# Stepping_Motor_DriverD.net
KiCad netlist of a schematic drawn in Altium Designer
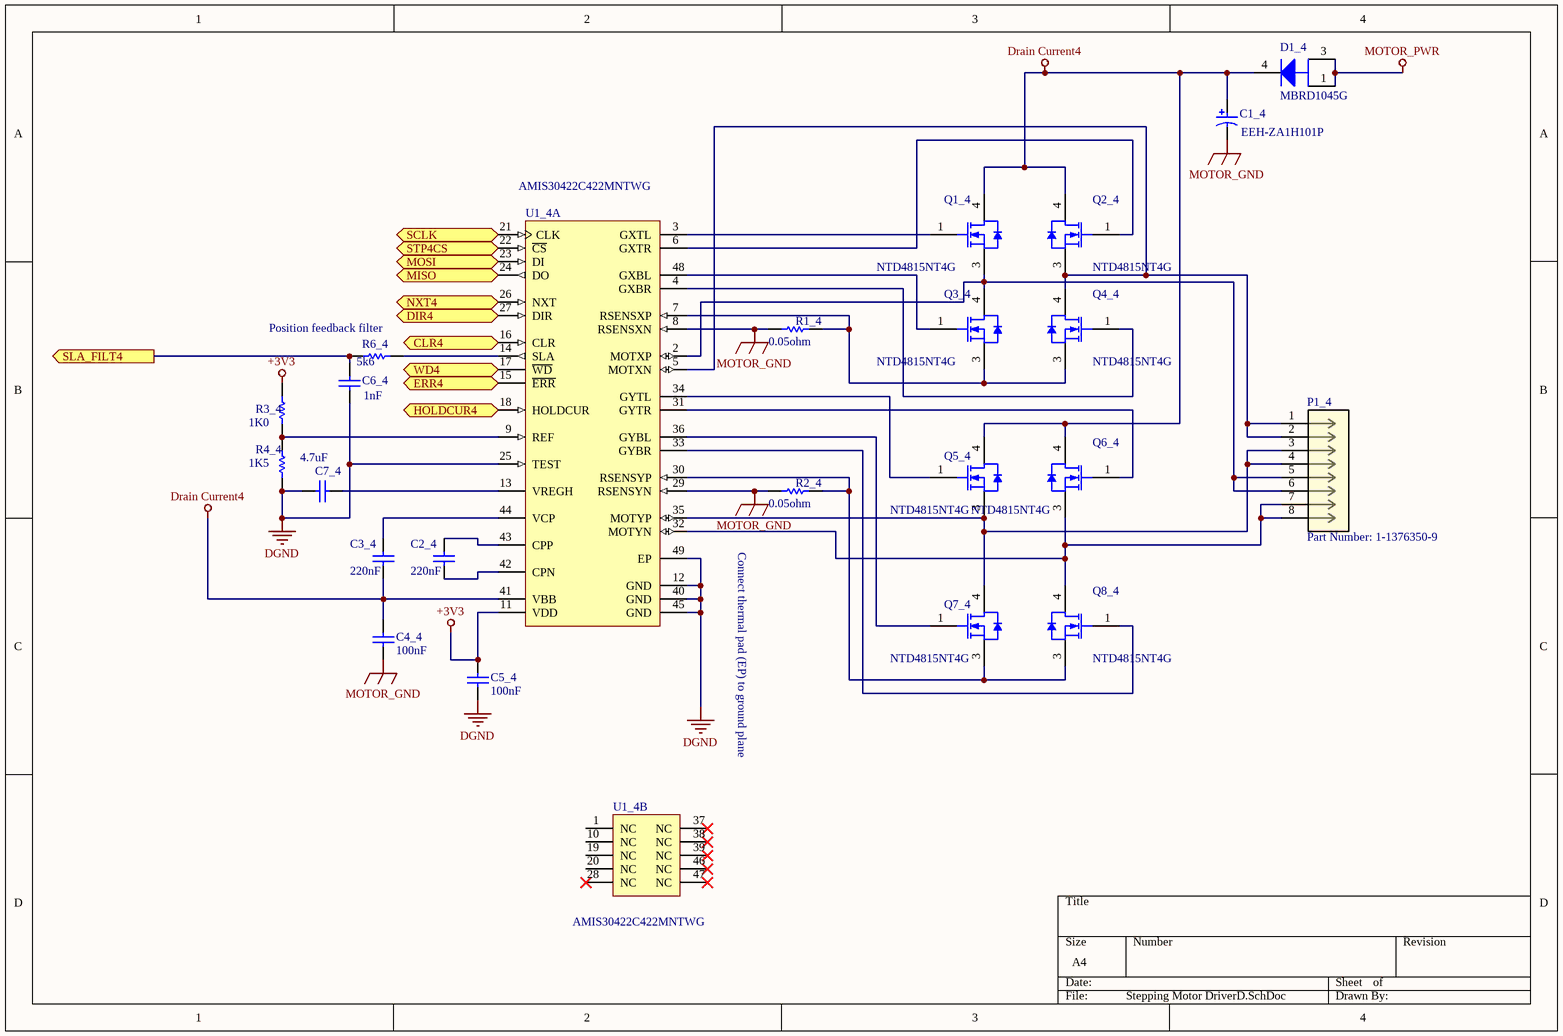
[diagram p0: Stepping Motor DriverD.SchDoc]

(export (version "E")
  (design (tool "Eeschema 10.0.6"))
  (components
    (comp (ref "C1_4")
      (value "EEH-ZA1H101P")
      (footprint "PNSC-ZA-G_L")
      (fields (field (name "TOLERANCE") "20%") (field (name "MANUFACTURER") "Panasonic"))
      (libsource (lib "Altium Content Vault") (part "CAP-P-2"))
    )
    (comp (ref "C2_4")
      (value "220nF")
      (footprint "CAPC0805(2012)75_L")
      (description "CAP 220nF 50V -20% to +80% 0805 (2012 Metric) Thickness 0.75mm SMD")
      (fields (field (name "TOLERANCE") "-20% to +80%") (field (name "Comment") "CAP 220nF 50V 0805(2012)"))
      (libsource (lib "Altium Content Vault") (part "CMP-1036-04556-1"))
    )
    (comp (ref "C3_4")
      (value "220nF")
      (footprint "CAPC0805(2012)75_L")
      (description "CAP 220nF 50V -20% to +80% 0805 (2012 Metric) Thickness 0.75mm SMD")
      (fields (field (name "TOLERANCE") "-20% to +80%") (field (name "Comment") "CAP 220nF 50V 0805(2012)"))
      (libsource (lib "Altium Content Vault") (part "CMP-1036-04556-1"))
    )
    (comp (ref "C4_4")
      (value "100nF")
      (footprint "CAPC1812(4532)110_N")
      (description "CAP 100nF 50V ±20% 1812 (4532 Metric) Thickness 1.1mm SMD")
      (fields (field (name "TOLERANCE") "Â±20%") (field (name "Comment") "CAP 100nF 50V 1812(4532)"))
      (libsource (lib "Altium Content Vault") (part "CMP-1040-01292-1"))
    )
    (comp (ref "C5_4")
      (value "100nF")
      (footprint "CAPC1812(4532)110_N")
      (description "CAP 100nF 50V ±20% 1812 (4532 Metric) Thickness 1.1mm SMD")
      (fields (field (name "TOLERANCE") "Â±20%") (field (name "Comment") "CAP 100nF 50V 1812(4532)"))
      (libsource (lib "Altium Content Vault") (part "CMP-1040-01292-1"))
    )
    (comp (ref "C6_4")
      (value "1nF")
      (footprint "CAPC1206(3216)170_N")
      (description "CAP 1nF 50V ±2% 1206 (3216 Metric) Thickness 1.7mm SMD")
      (fields (field (name "TOLERANCE") "Â±2%") (field (name "Comment") "CAP 1nF 50V 1206(3216)"))
      (libsource (lib "Altium Content Vault") (part "CMP-1037-02447-1"))
    )
    (comp (ref "C7_4")
      (value "4.7uF")
      (footprint "CAPC2220(5750)230_L")
      (description "CAP 4.7uF 50V ±10% 2220 (5750 Metric) Thickness 2.2mm SMD")
      (fields (field (name "TOLERANCE") "Â±10%") (field (name "Comment") "CAP 4.7uF 50V 2220(5750)"))
      (libsource (lib "Altium Content Vault") (part "CMP-1042-00755-1"))
    )
    (comp (ref "D1_4")
      (value "MBRD1045G")
      (footprint "ONSC-DPAK-3-369C-01_V")
      (description "SWITCHMODE(TM) Schottky Power Rectifier, 3-Pin DPAK, Pb-Free, Tube")
      (fields (field (name "MANUFACTURER") "On Semiconductor"))
      (libsource (lib "Altium Content Vault") (part "ONSC-D-A1A3K4-3_A"))
    )
    (comp (ref "P1_4")
      (value "Part Number: 1-1376350-9")
      (footprint "conn8_1-1376350-")
      (description "025 8POS CAP ASSY H TIN")
      (fields
        (field (name "MANUFACTURER_PART_NUMBER") "1-1376350-9")
        (field (name "COPYRIGHT") "Copyright (C) 2018 Accelerated Designs. All rights reserved")
      )
      (libsource (lib "2020-04-08_04-40-03") (part "1-1376350-9"))
    )
    (comp (ref "Q1_4")
      (value "NTD4815NT4G")
      (footprint "ONSC-DPAK-3-369AA-01_V")
      (description "Power MOSFET, 30 V, 35 A, Single N-Channel, 3-Pin DPAK, Pb-Free, Tape and Reel")
      (fields (field (name "MANUFACTURER") "On Semiconductor"))
      (libsource (lib "Altium Content Vault") (part "ONSC-NMOS-G1S3D4-3_B"))
    )
    (comp (ref "Q2_4")
      (value "NTD4815NT4G")
      (footprint "ONSC-DPAK-3-369AA-01_V")
      (description "Power MOSFET, 30 V, 35 A, Single N-Channel, 3-Pin DPAK, Pb-Free, Tape and Reel")
      (fields (field (name "MANUFACTURER") "On Semiconductor"))
      (libsource (lib "Altium Content Vault") (part "CMP-1058-00298-1"))
    )
    (comp (ref "Q3_4")
      (value "NTD4815NT4G")
      (footprint "ONSC-DPAK-3-369AA-01_V")
      (description "Power MOSFET, 30 V, 35 A, Single N-Channel, 3-Pin DPAK, Pb-Free, Tape and Reel")
      (fields (field (name "MANUFACTURER") "On Semiconductor"))
      (libsource (lib "Altium Content Vault") (part "ONSC-NMOS-G1S3D4-3_B"))
    )
    (comp (ref "Q4_4")
      (value "NTD4815NT4G")
      (footprint "ONSC-DPAK-3-369AA-01_V")
      (description "Power MOSFET, 30 V, 35 A, Single N-Channel, 3-Pin DPAK, Pb-Free, Tape and Reel")
      (fields (field (name "MANUFACTURER") "On Semiconductor"))
      (libsource (lib "Altium Content Vault") (part "CMP-1058-00298-1"))
    )
    (comp (ref "Q5_4")
      (value "NTD4815NT4G")
      (footprint "ONSC-DPAK-3-369AA-01_V")
      (description "Power MOSFET, 30 V, 35 A, Single N-Channel, 3-Pin DPAK, Pb-Free, Tape and Reel")
      (fields (field (name "MANUFACTURER") "On Semiconductor"))
      (libsource (lib "Altium Content Vault") (part "ONSC-NMOS-G1S3D4-3_B"))
    )
    (comp (ref "Q6_4")
      (value "NTD4815NT4G")
      (footprint "ONSC-DPAK-3-369AA-01_V")
      (description "Power MOSFET, 30 V, 35 A, Single N-Channel, 3-Pin DPAK, Pb-Free, Tape and Reel")
      (fields (field (name "MANUFACTURER") "On Semiconductor"))
      (libsource (lib "Altium Content Vault") (part "CMP-1058-00298-1"))
    )
    (comp (ref "Q7_4")
      (value "NTD4815NT4G")
      (footprint "ONSC-DPAK-3-369AA-01_V")
      (description "Power MOSFET, 30 V, 35 A, Single N-Channel, 3-Pin DPAK, Pb-Free, Tape and Reel")
      (fields (field (name "MANUFACTURER") "On Semiconductor"))
      (libsource (lib "Altium Content Vault") (part "ONSC-NMOS-G1S3D4-3_B"))
    )
    (comp (ref "Q8_4")
      (value "NTD4815NT4G")
      (footprint "ONSC-DPAK-3-369AA-01_V")
      (description "Power MOSFET, 30 V, 35 A, Single N-Channel, 3-Pin DPAK, Pb-Free, Tape and Reel")
      (fields (field (name "MANUFACTURER") "On Semiconductor"))
      (libsource (lib "Altium Content Vault") (part "CMP-1058-00298-1"))
    )
    (comp (ref "R1_4")
      (value "WSL2512R0500FEA")
      (footprint "RESC6432X89X76LL25T25")
      (description "Chip Resistor, 50 mOhm, +/- 1%, 1 W, -65 to 170 degC, 2512 (6432 Metric), RoHS, Tape and Reel")
      (fields (field (name "MANUFACTURER") "Vishay") (field (name "RESISTANCE") "0.05ohm"))
      (libsource (lib "Altium Content Vault") (part "CMP-2000-07420-1"))
    )
    (comp (ref "R2_4")
      (value "WSL2512R0500FEA")
      (footprint "RESC6432X89X76LL25T25")
      (description "Chip Resistor, 50 mOhm, +/- 1%, 1 W, -65 to 170 degC, 2512 (6432 Metric), RoHS, Tape and Reel")
      (fields (field (name "MANUFACTURER") "Vishay") (field (name "RESISTANCE") "0.05ohm"))
      (libsource (lib "Altium Content Vault") (part "CMP-2000-07420-1"))
    )
    (comp (ref "R3_4")
      (value "1K0")
      (footprint "RESC0805(2012)_M")
      (description "1K 0.125W 1% 0805 (2012 Metric)  SMD")
      (fields (field (name "TOLERANCE") "1 %") (field (name "POWER") "0.125 W"))
      (libsource (lib "Altium Content Vault") (part "CMP-1013-00510-1"))
    )
    (comp (ref "R4_4")
      (value "1K5")
      (footprint "RESC0805(2012)_M")
      (description "1K5 0.125W 1% 0805 (2012 Metric)  SMD")
      (fields (field (name "POWER") "0.125 W") (field (name "TOLERANCE") "1 %"))
      (libsource (lib "Altium Content Vault") (part "CMP-1013-00528-1"))
    )
    (comp (ref "R6_4")
      (value "5k6")
      (footprint "RESC0805(2012)_L")
      (description "5K6 0.125W 1% 0805 (2012 Metric)  SMD")
      (fields (field (name "POWER") "0.125 W") (field (name "TOLERANCE") "1 %"))
      (libsource (lib "Altium Content Vault") (part "CMP-1013-00595-1"))
    )
    (comp (ref "U1_4")
      (value "AMIS30422C422MNTWG")
      (footprint "ONSC-QFN-48-485AJ-01_V")
      (fields (field (name "MANUFACTURER") "ON Semiconductor"))
      (libsource (lib "Altium Content Vault") (part "ONSC-AMIS-30422-QFN-48"))
    )
  )
  (nets
    (net (code "1") (name "+3V3") (class "Default")
      (node (ref "C5_4") (pin "2") (pinfunction "2_2") (pintype "passive"))
      (node (ref "R3_4") (pin "2") (pinfunction "2_2") (pintype "passive"))
      (node (ref "U1_4") (pin "11") (pinfunction "VDD_11") (pintype "power_in"))
    )
    (net (code "2") (name "/CLR4") (class "Default")
      (node (ref "U1_4") (pin "16") (pinfunction "CLR_16") (pintype "input"))
    )
    (net (code "3") (name "/DIR4") (class "Default")
      (node (ref "U1_4") (pin "27") (pinfunction "DIR_27") (pintype "input"))
    )
    (net (code "4") (name "/ERR4") (class "Default")
      (node (ref "U1_4") (pin "15") (pinfunction "~{ERR}_15") (pintype "tri_state"))
    )
    (net (code "5") (name "/HOLDCUR4") (class "Default")
      (node (ref "U1_4") (pin "18") (pinfunction "HOLDCUR_18") (pintype "input"))
    )
    (net (code "6") (name "/MISO") (class "Default")
      (node (ref "U1_4") (pin "24") (pinfunction "DO_24") (pintype "output"))
    )
    (net (code "7") (name "/MOSI") (class "Default")
      (node (ref "U1_4") (pin "23") (pinfunction "DI_23") (pintype "input"))
    )
    (net (code "8") (name "/NXT4") (class "Default")
      (node (ref "U1_4") (pin "26") (pinfunction "NXT_26") (pintype "input"))
    )
    (net (code "9") (name "/SCLK") (class "Default")
      (node (ref "U1_4") (pin "21") (pinfunction "CLK_21") (pintype "input"))
    )
    (net (code "10") (name "/SLA_FILT4") (class "Default")
      (node (ref "C6_4") (pin "2") (pinfunction "2_2") (pintype "passive"))
      (node (ref "R6_4") (pin "1") (pinfunction "1_1") (pintype "passive"))
    )
    (net (code "11") (name "/STP4CS") (class "Default")
      (node (ref "U1_4") (pin "22") (pinfunction "~{CS}_22") (pintype "input"))
    )
    (net (code "12") (name "/WD4") (class "Default")
      (node (ref "U1_4") (pin "17") (pinfunction "~{WD}_17") (pintype "tri_state"))
    )
    (net (code "13") (name "DGND") (class "Default")
      (node (ref "C5_4") (pin "1") (pinfunction "1_1") (pintype "passive"))
      (node (ref "C6_4") (pin "1") (pinfunction "1_1") (pintype "passive"))
      (node (ref "C7_4") (pin "1") (pinfunction "1_1") (pintype "passive"))
      (node (ref "R4_4") (pin "1") (pinfunction "1_1") (pintype "passive"))
      (node (ref "U1_4") (pin "12") (pinfunction "GND_12") (pintype "power_in"))
      (node (ref "U1_4") (pin "25") (pinfunction "TEST_25") (pintype "input"))
      (node (ref "U1_4") (pin "40") (pinfunction "GND_40") (pintype "power_in"))
      (node (ref "U1_4") (pin "45") (pinfunction "GND_45") (pintype "power_in"))
      (node (ref "U1_4") (pin "49") (pinfunction "EP_49") (pintype "passive"))
    )
    (net (code "14") (name "Drain Current4") (class "Default")
      (node (ref "C1_4") (pin "1") (pinfunction "1_1") (pintype "passive"))
      (node (ref "C3_4") (pin "1") (pinfunction "1_1") (pintype "passive"))
      (node (ref "C4_4") (pin "2") (pinfunction "2_2") (pintype "passive"))
      (node (ref "D1_4") (pin "4") (pinfunction "K_4") (pintype "passive"))
      (node (ref "Q1_4") (pin "4") (pinfunction "D_4") (pintype "passive"))
      (node (ref "Q2_4") (pin "4") (pinfunction "D_4") (pintype "passive"))
      (node (ref "Q5_4") (pin "4") (pinfunction "D_4") (pintype "passive"))
      (node (ref "Q6_4") (pin "4") (pinfunction "D_4") (pintype "passive"))
      (node (ref "U1_4") (pin "41") (pinfunction "VBB_41") (pintype "power_in"))
    )
    (net (code "15") (name "MOTOR_GND") (class "Default")
      (node (ref "C1_4") (pin "2") (pinfunction "2_2") (pintype "passive"))
      (node (ref "C4_4") (pin "1") (pinfunction "1_1") (pintype "passive"))
      (node (ref "R1_4") (pin "1") (pinfunction "1_1") (pintype "passive"))
      (node (ref "R2_4") (pin "1") (pinfunction "1_1") (pintype "passive"))
      (node (ref "U1_4") (pin "29") (pinfunction "RSENSYN_29") (pintype "input"))
      (node (ref "U1_4") (pin "8") (pinfunction "RSENSXN_8") (pintype "input"))
    )
    (net (code "16") (name "MOTOR_PWR") (class "Default")
      (node (ref "D1_4") (pin "1") (pinfunction "A_1") (pintype "passive"))
      (node (ref "D1_4") (pin "3") (pinfunction "A_3") (pintype "passive"))
    )
    (net (code "17") (name "Net-(Q1_4-G)") (class "Default")
      (node (ref "Q1_4") (pin "1") (pinfunction "G_1") (pintype "passive"))
      (node (ref "U1_4") (pin "3") (pinfunction "GXTL_3") (pintype "tri_state"))
    )
    (net (code "18") (name "Net-(Q1_4-S)") (class "Default")
      (node (ref "P1_4") (pin "5") (pinfunction "5_5") (pintype "passive"))
      (node (ref "P1_4") (pin "6") (pinfunction "6_6") (pintype "passive"))
      (node (ref "Q1_4") (pin "3") (pinfunction "S_3") (pintype "passive"))
      (node (ref "Q3_4") (pin "4") (pinfunction "D_4") (pintype "passive"))
      (node (ref "U1_4") (pin "2") (pinfunction "MOTXP_2") (pintype "bidirectional"))
    )
    (net (code "19") (name "Net-(Q2_4-G)") (class "Default")
      (node (ref "Q2_4") (pin "1") (pinfunction "G_1") (pintype "passive"))
      (node (ref "U1_4") (pin "6") (pinfunction "GXTR_6") (pintype "tri_state"))
    )
    (net (code "20") (name "Net-(Q2_4-S)") (class "Default")
      (node (ref "P1_4") (pin "1") (pinfunction "1_1") (pintype "passive"))
      (node (ref "P1_4") (pin "2") (pinfunction "2_2") (pintype "passive"))
      (node (ref "Q2_4") (pin "3") (pinfunction "S_3") (pintype "passive"))
      (node (ref "Q4_4") (pin "4") (pinfunction "D_4") (pintype "passive"))
      (node (ref "U1_4") (pin "5") (pinfunction "MOTXN_5") (pintype "bidirectional"))
    )
    (net (code "21") (name "Net-(Q3_4-G)") (class "Default")
      (node (ref "Q3_4") (pin "1") (pinfunction "G_1") (pintype "passive"))
      (node (ref "U1_4") (pin "48") (pinfunction "GXBL_48") (pintype "tri_state"))
    )
    (net (code "22") (name "Net-(Q3_4-S)") (class "Default")
      (node (ref "Q3_4") (pin "3") (pinfunction "S_3") (pintype "passive"))
      (node (ref "Q4_4") (pin "3") (pinfunction "S_3") (pintype "passive"))
      (node (ref "R1_4") (pin "2") (pinfunction "2_2") (pintype "passive"))
      (node (ref "U1_4") (pin "7") (pinfunction "RSENSXP_7") (pintype "input"))
    )
    (net (code "23") (name "Net-(Q4_4-G)") (class "Default")
      (node (ref "Q4_4") (pin "1") (pinfunction "G_1") (pintype "passive"))
      (node (ref "U1_4") (pin "4") (pinfunction "GXBR_4") (pintype "tri_state"))
    )
    (net (code "24") (name "Net-(Q5_4-G)") (class "Default")
      (node (ref "Q5_4") (pin "1") (pinfunction "G_1") (pintype "passive"))
      (node (ref "U1_4") (pin "34") (pinfunction "GYTL_34") (pintype "tri_state"))
    )
    (net (code "25") (name "Net-(Q5_4-S)") (class "Default")
      (node (ref "P1_4") (pin "3") (pinfunction "3_3") (pintype "passive"))
      (node (ref "P1_4") (pin "4") (pinfunction "4_4") (pintype "passive"))
      (node (ref "Q5_4") (pin "3") (pinfunction "S_3") (pintype "passive"))
      (node (ref "Q7_4") (pin "4") (pinfunction "D_4") (pintype "passive"))
      (node (ref "U1_4") (pin "35") (pinfunction "MOTYP_35") (pintype "bidirectional"))
    )
    (net (code "26") (name "Net-(Q6_4-G)") (class "Default")
      (node (ref "Q6_4") (pin "1") (pinfunction "G_1") (pintype "passive"))
      (node (ref "U1_4") (pin "31") (pinfunction "GYTR_31") (pintype "tri_state"))
    )
    (net (code "27") (name "Net-(Q6_4-S)") (class "Default")
      (node (ref "P1_4") (pin "7") (pinfunction "7_7") (pintype "passive"))
      (node (ref "P1_4") (pin "8") (pinfunction "8_8") (pintype "passive"))
      (node (ref "Q6_4") (pin "3") (pinfunction "S_3") (pintype "passive"))
      (node (ref "Q8_4") (pin "4") (pinfunction "D_4") (pintype "passive"))
      (node (ref "U1_4") (pin "32") (pinfunction "MOTYN_32") (pintype "bidirectional"))
    )
    (net (code "28") (name "Net-(Q7_4-G)") (class "Default")
      (node (ref "Q7_4") (pin "1") (pinfunction "G_1") (pintype "passive"))
      (node (ref "U1_4") (pin "36") (pinfunction "GYBL_36") (pintype "tri_state"))
    )
    (net (code "29") (name "Net-(Q7_4-S)") (class "Default")
      (node (ref "Q7_4") (pin "3") (pinfunction "S_3") (pintype "passive"))
      (node (ref "Q8_4") (pin "3") (pinfunction "S_3") (pintype "passive"))
      (node (ref "R2_4") (pin "2") (pinfunction "2_2") (pintype "passive"))
      (node (ref "U1_4") (pin "30") (pinfunction "RSENSYP_30") (pintype "input"))
    )
    (net (code "30") (name "Net-(Q8_4-G)") (class "Default")
      (node (ref "Q8_4") (pin "1") (pinfunction "G_1") (pintype "passive"))
      (node (ref "U1_4") (pin "33") (pinfunction "GYBR_33") (pintype "tri_state"))
    )
    (net (code "31") (name "Net-(U1_4A-CPN)") (class "Default")
      (node (ref "C2_4") (pin "1") (pinfunction "1_1") (pintype "passive"))
      (node (ref "U1_4") (pin "42") (pinfunction "CPN_42") (pintype "passive"))
    )
    (net (code "32") (name "Net-(U1_4A-CPP)") (class "Default")
      (node (ref "C2_4") (pin "2") (pinfunction "2_2") (pintype "passive"))
      (node (ref "U1_4") (pin "43") (pinfunction "CPP_43") (pintype "passive"))
    )
    (net (code "33") (name "Net-(U1_4A-REF)") (class "Default")
      (node (ref "R3_4") (pin "1") (pinfunction "1_1") (pintype "passive"))
      (node (ref "R4_4") (pin "2") (pinfunction "2_2") (pintype "passive"))
      (node (ref "U1_4") (pin "9") (pinfunction "REF_9") (pintype "input"))
    )
    (net (code "34") (name "Net-(U1_4A-SLA)") (class "Default")
      (node (ref "R6_4") (pin "2") (pinfunction "2_2") (pintype "passive"))
      (node (ref "U1_4") (pin "14") (pinfunction "SLA_14") (pintype "output"))
    )
    (net (code "35") (name "Net-(U1_4A-VCP)") (class "Default")
      (node (ref "C3_4") (pin "2") (pinfunction "2_2") (pintype "passive"))
      (node (ref "U1_4") (pin "44") (pinfunction "VCP_44") (pintype "passive"))
    )
    (net (code "36") (name "Net-(U1_4A-VREGH)") (class "Default")
      (node (ref "C7_4") (pin "2") (pinfunction "2_2") (pintype "passive"))
      (node (ref "U1_4") (pin "13") (pinfunction "VREGH_13") (pintype "power_in"))
    )
    (net (code "37") (name "unconnected-(U1_4B-NC-Pad1)") (class "Default")
      (node (ref "U1_4") (pin "1") (pinfunction "NC_1") (pintype "passive"))
    )
    (net (code "38") (name "unconnected-(U1_4B-NC-Pad10)") (class "Default")
      (node (ref "U1_4") (pin "10") (pinfunction "NC_10") (pintype "passive"))
    )
    (net (code "39") (name "unconnected-(U1_4B-NC-Pad19)") (class "Default")
      (node (ref "U1_4") (pin "19") (pinfunction "NC_19") (pintype "passive"))
    )
    (net (code "40") (name "unconnected-(U1_4B-NC-Pad20)") (class "Default")
      (node (ref "U1_4") (pin "20") (pinfunction "NC_20") (pintype "passive"))
    )
    (net (code "41") (name "unconnected-(U1_4B-NC-Pad28)") (class "Default")
      (node (ref "U1_4") (pin "28") (pinfunction "NC_28") (pintype "passive+no_connect"))
    )
    (net (code "42") (name "unconnected-(U1_4B-NC-Pad37)") (class "Default")
      (node (ref "U1_4") (pin "37") (pinfunction "NC_37") (pintype "passive+no_connect"))
    )
    (net (code "43") (name "unconnected-(U1_4B-NC-Pad38)") (class "Default")
      (node (ref "U1_4") (pin "38") (pinfunction "NC_38") (pintype "passive+no_connect"))
    )
    (net (code "44") (name "unconnected-(U1_4B-NC-Pad39)") (class "Default")
      (node (ref "U1_4") (pin "39") (pinfunction "NC_39") (pintype "passive+no_connect"))
    )
    (net (code "45") (name "unconnected-(U1_4B-NC-Pad46)") (class "Default")
      (node (ref "U1_4") (pin "46") (pinfunction "NC_46") (pintype "passive+no_connect"))
    )
    (net (code "46") (name "unconnected-(U1_4B-NC-Pad47)") (class "Default")
      (node (ref "U1_4") (pin "47") (pinfunction "NC_47") (pintype "passive+no_connect"))
    )
  )
)
